# design.net
KiCad netlist of a schematic drawn in EasyEDA Pro
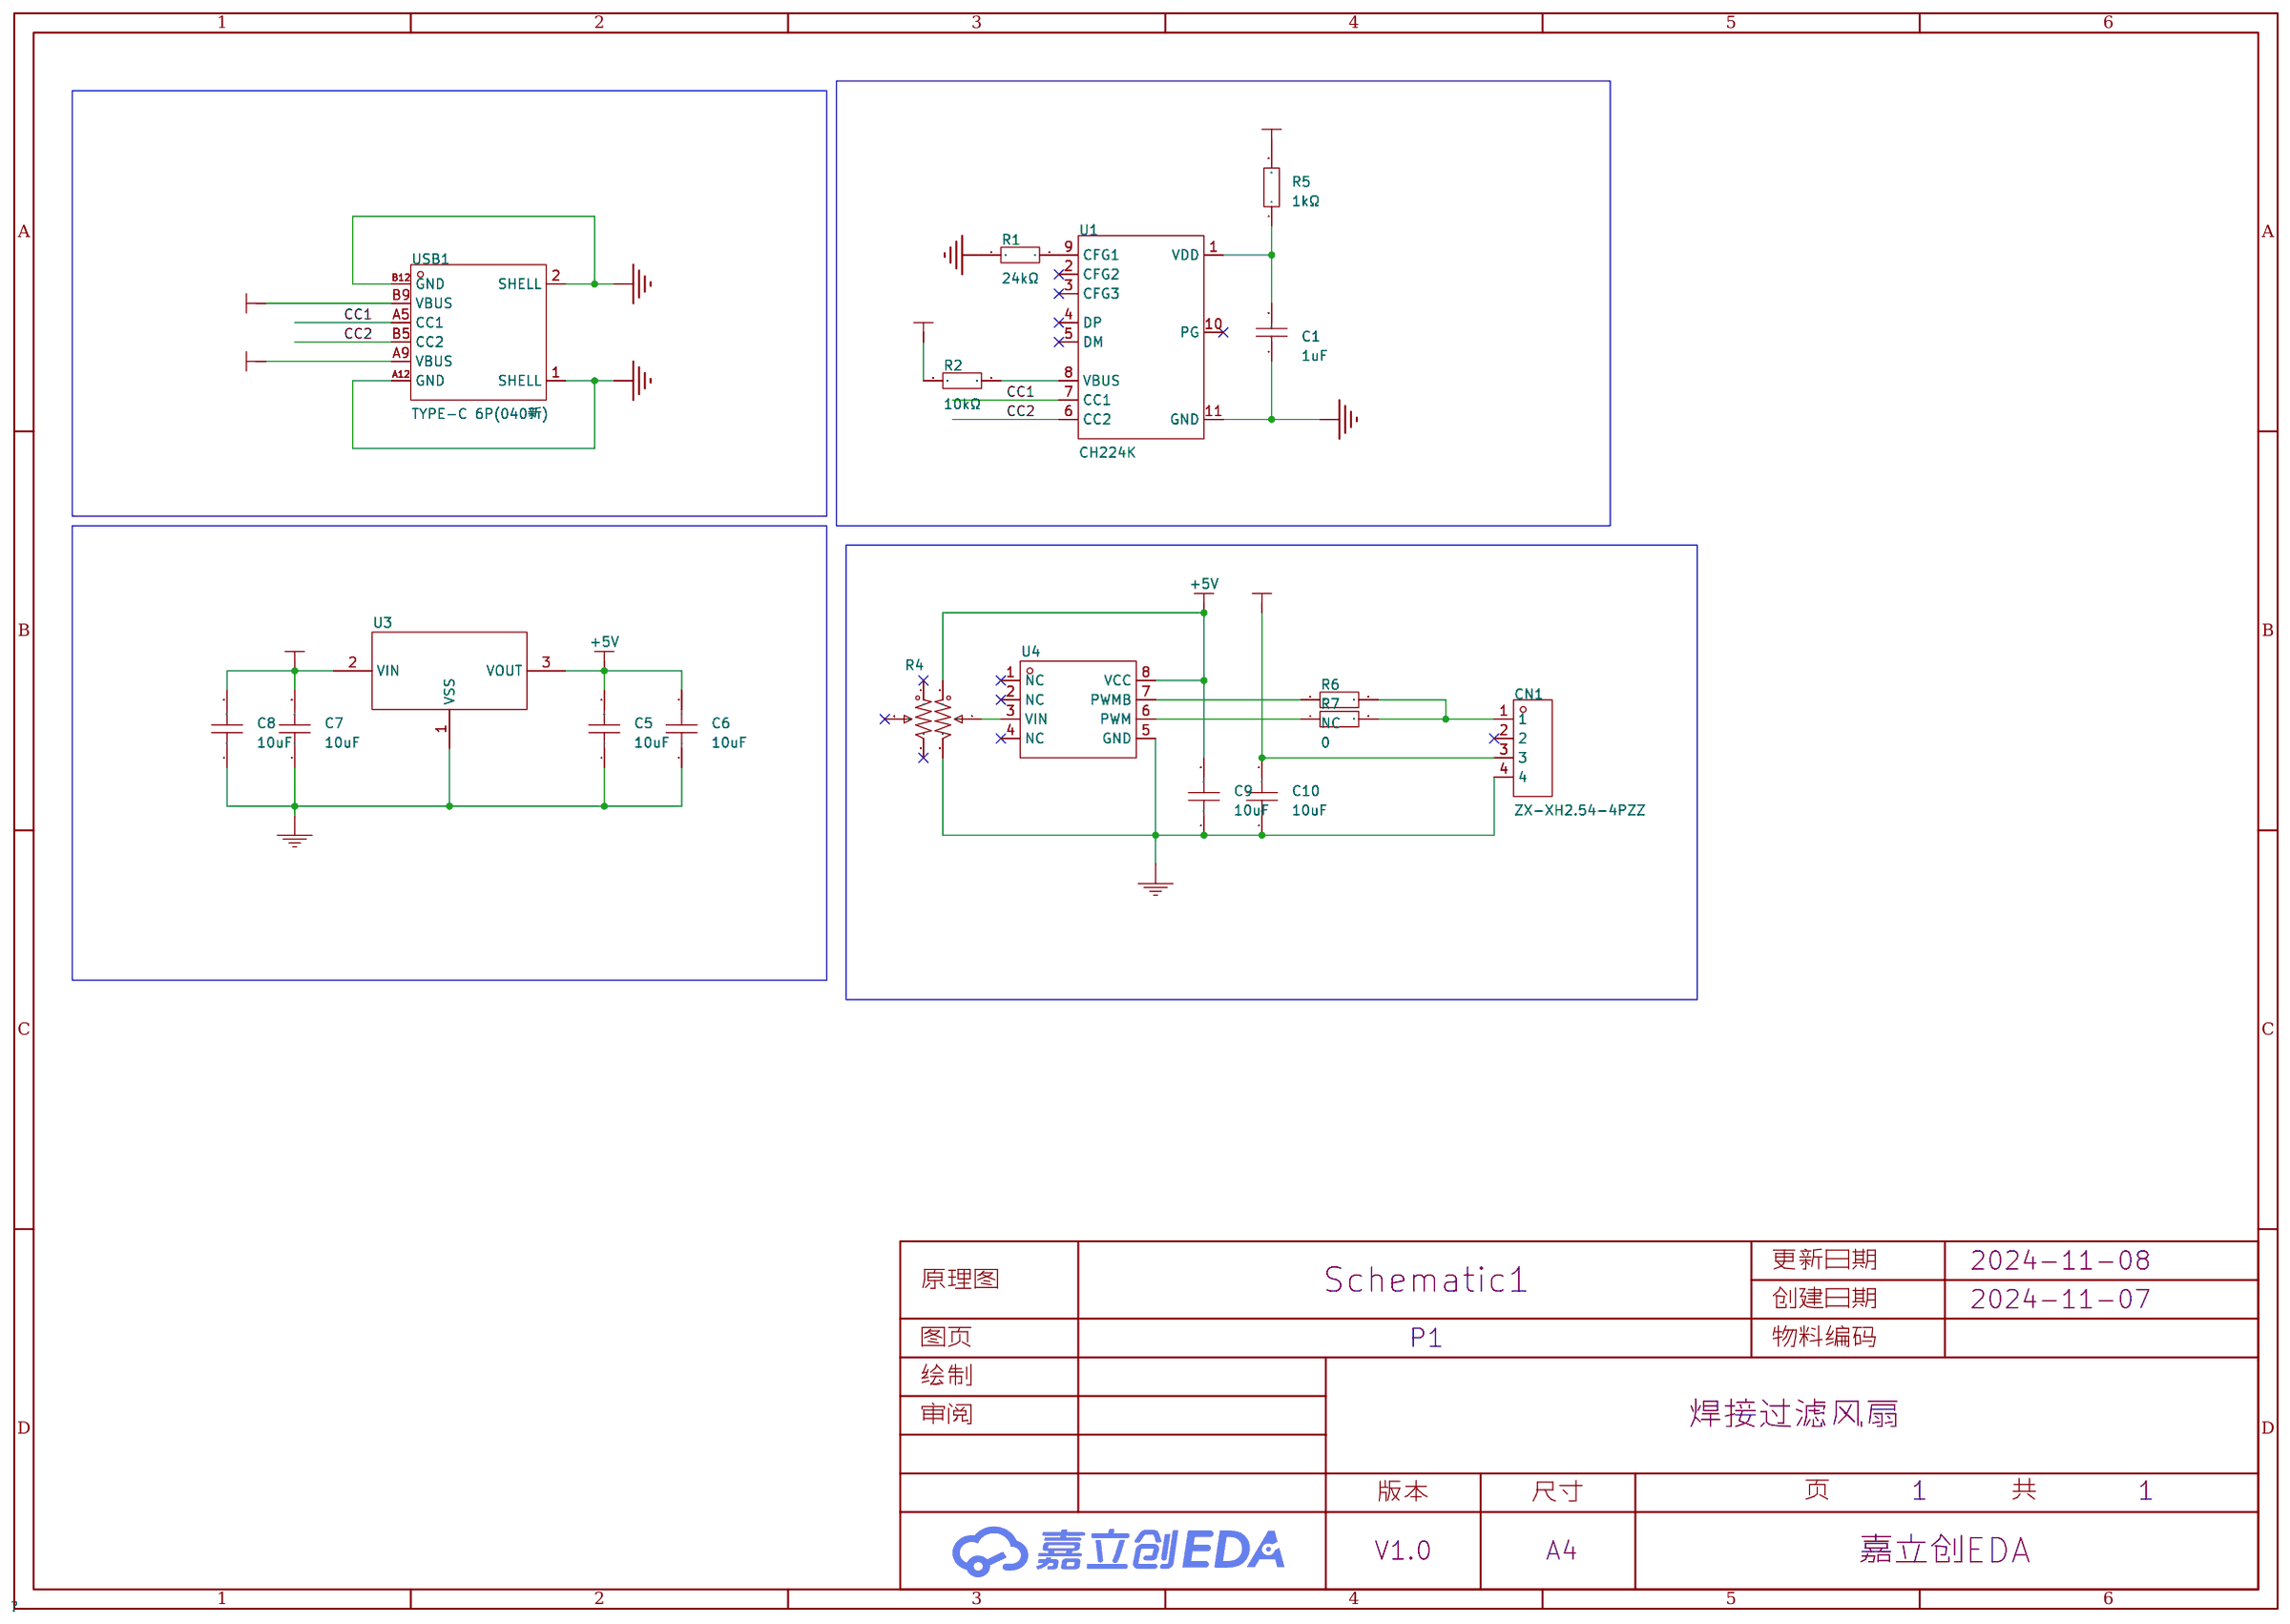
[diagram p0: schematic sheet]

(export (version "E")
  (design (tool "Eeschema 10.0.6"))
  (components
    (comp (ref "C1")
      (value "1uF")
      (footprint "easyedapro:C0805")
      (description "容值:1uF;精度:±10%;额定电压:50V;材质(温度系数):X7R;")
      (fields
        (field (name "Manufacturer Part") "CL21B105KBFNNNE")
        (field (name "Manufacturer") "SAMSUNG(三星)")
      )
      (libsource (lib "easyedapro") (part "CL21B105KBFNNNE"))
    )
    (comp (ref "C5")
      (value "10uF")
      (footprint "easyedapro:C0805")
      (description "容值:10uF;精度:±10%;额定电压:35V;材质(温度系数):X5R;")
      (fields
        (field (name "Manufacturer Part") "CGA0805X5R106K350MT")
        (field (name "Manufacturer") "HRE(芯声)")
      )
      (libsource (lib "easyedapro") (part "CGA0805X5R106K350MT"))
    )
    (comp (ref "C6")
      (value "10uF")
      (footprint "easyedapro:C0805")
      (description "容值:10uF;精度:±10%;额定电压:35V;材质(温度系数):X5R;")
      (fields
        (field (name "Manufacturer Part") "CGA0805X5R106K350MT")
        (field (name "Manufacturer") "HRE(芯声)")
      )
      (libsource (lib "easyedapro") (part "CGA0805X5R106K350MT"))
    )
    (comp (ref "C7")
      (value "10uF")
      (footprint "easyedapro:C0805")
      (description "容值:10uF;精度:±10%;额定电压:35V;材质(温度系数):X5R;")
      (fields
        (field (name "Manufacturer Part") "CGA0805X5R106K350MT")
        (field (name "Manufacturer") "HRE(芯声)")
      )
      (libsource (lib "easyedapro") (part "CGA0805X5R106K350MT"))
    )
    (comp (ref "C8")
      (value "10uF")
      (footprint "easyedapro:C0805")
      (description "容值:10uF;精度:±10%;额定电压:35V;材质(温度系数):X5R;")
      (fields
        (field (name "Manufacturer Part") "CGA0805X5R106K350MT")
        (field (name "Manufacturer") "HRE(芯声)")
      )
      (libsource (lib "easyedapro") (part "CGA0805X5R106K350MT"))
    )
    (comp (ref "C9")
      (value "10uF")
      (footprint "easyedapro:C0805")
      (description "容值:10uF;精度:±10%;额定电压:35V;材质(温度系数):X5R;")
      (fields
        (field (name "Manufacturer Part") "CGA0805X5R106K350MT")
        (field (name "Manufacturer") "HRE(芯声)")
      )
      (libsource (lib "easyedapro") (part "CGA0805X5R106K350MT"))
    )
    (comp (ref "C10")
      (value "10uF")
      (footprint "easyedapro:C0805")
      (description "容值:10uF;精度:±10%;额定电压:35V;材质(温度系数):X5R;")
      (fields
        (field (name "Manufacturer Part") "CGA0805X5R106K350MT")
        (field (name "Manufacturer") "HRE(芯声)")
      )
      (libsource (lib "easyedapro") (part "CGA0805X5R106K350MT"))
    )
    (comp (ref "CN1")
      (value "ZX-XH2.54-4PZZ")
      (footprint "easyedapro:CONN-TH_4P-P2.50_4PIN")
      (fields (field (name "Manufacturer") "Megastar(兆星)"))
      (libsource (lib "easyedapro") (part "ZX-XH2.54-4PZZ"))
    )
    (comp (ref "R1")
      (value "24kΩ")
      (footprint "easyedapro:R0805")
      (description "电阻类型:厚膜电阻;阻值:24kΩ;精度:±1%;功率:125mW;最大工作电压:150V;温度系数:±100ppm/°C;")
      (fields
        (field (name "Manufacturer Part") "0805W8F2402T5E")
        (field (name "Manufacturer") "UNI-ROYAL(厚声)")
      )
      (libsource (lib "easyedapro") (part "0805W8F2402T5E"))
    )
    (comp (ref "R2")
      (value "10kΩ")
      (footprint "easyedapro:R0805")
      (description "电阻类型:厚膜电阻;阻值:10kΩ;精度:±5%;功率:125mW;最大工作电压:150V;温度系数:±100ppm/°C;")
      (fields
        (field (name "Manufacturer Part") "0805W8J0103T5E")
        (field (name "Manufacturer") "UNI-ROYAL(厚声)")
      )
      (libsource (lib "easyedapro") (part "0805W8J0103T5E"))
    )
    (comp (ref "R4")
      (value "100kΩ")
      (fields (field (name "Manufacturer") "ALPSALPINE(阿尔卑斯阿尔派)"))
      (libsource (lib "easyedapro") (part "RK09712200MY"))
    )
    (comp (ref "R5")
      (value "1kΩ")
      (footprint "easyedapro:R0805")
      (description "电阻类型:厚膜电阻;阻值:1kΩ;精度:±1%;功率:125mW;最大工作电压:150V;温度系数:±100ppm/°C;")
      (fields
        (field (name "Manufacturer Part") "0805W8F1001T5E")
        (field (name "Manufacturer") "UNI-ROYAL(厚声)")
      )
      (libsource (lib "easyedapro") (part "0805W8F1001T5E"))
    )
    (comp (ref "R6")
      (value "NC")
      (footprint "easyedapro:R0805")
      (description "电阻类型:厚膜电阻;阻值:10kΩ;精度:±5%;功率:125mW;最大工作电压:150V;温度系数:±100ppm/°C;")
      (fields
        (field (name "Manufacturer Part") "0805W8J0103T5E")
        (field (name "Manufacturer") "UNI-ROYAL(厚声)")
      )
      (libsource (lib "easyedapro") (part "0805W8J0103T5E"))
    )
    (comp (ref "R7")
      (value "0")
      (footprint "easyedapro:R0805")
      (description "电阻类型:厚膜电阻;阻值:10kΩ;精度:±5%;功率:125mW;最大工作电压:150V;温度系数:±100ppm/°C;")
      (fields
        (field (name "Manufacturer Part") "0805W8J0103T5E")
        (field (name "Manufacturer") "UNI-ROYAL(厚声)")
      )
      (libsource (lib "easyedapro") (part "0805W8J0103T5E"))
    )
    (comp (ref "U1")
      (value "CH224K")
      (footprint "easyedapro:ESSOP-10_L4.9-W3.9-P1.0-LS6.0-TL-EP")
      (description "应用功能:USB充电芯片;")
      (fields (field (name "Manufacturer") "WCH(南京沁恒)"))
      (libsource (lib "easyedapro") (part "CH224K"))
    )
    (comp (ref "U3")
      (value "ME6203A50PG")
      (fields (field (name "Manufacturer") "MICRONE(南京微盟)"))
      (libsource (lib "easyedapro") (part "ME6203A50PG"))
    )
    (comp (ref "U4")
      (value "GP9101-F20K-L2H1-SW")
      (footprint "easyedapro:SOP-8_L5.0-W3.9-P1.27-LS6.0-BL")
      (description "GP9101 0-VCC转PWM 20KHz L2H1")
      (fields (field (name "Manufacturer") "Guestgood(客益)"))
      (libsource (lib "easyedapro") (part "GP9101-F20K-L2H1-SW"))
    )
    (comp (ref "USB1")
      (value "TYPE-C 6P(040新)")
      (footprint "easyedapro:USB-C-SMD_TYPE-C-6P")
      (description "连接器类型:Type-C;标准:USB 3.1;公母:母;安装方式:卧贴;触点数量:6P;端口数量:1;额定电流 - 电源:3A;工作温度范围:-40°C~+85°C;")
      (fields (field (name "Manufacturer") "SHOU HAN(首韩)"))
      (libsource (lib "easyedapro") (part "TYPE-C 6P(040新)"))
    )
  )
  (nets
    (net (code "1") (name "+5V") (class "Default")
      (node (ref "C5") (pin "2") (pinfunction "2_2") (pintype "unspecified"))
      (node (ref "C6") (pin "2") (pinfunction "2_2") (pintype "unspecified"))
      (node (ref "C9") (pin "2") (pinfunction "2_2") (pintype "unspecified"))
      (node (ref "R4") (pin "1") (pinfunction "1_1") (pintype "input"))
      (node (ref "U3") (pin "3") (pinfunction "VOUT_3") (pintype "input"))
      (node (ref "U4") (pin "8") (pinfunction "VCC_8") (pintype "input"))
    )
    (net (code "2") (name "+12V") (class "Default")
      (node (ref "C10") (pin "2") (pinfunction "2_2") (pintype "unspecified"))
      (node (ref "C7") (pin "2") (pinfunction "2_2") (pintype "unspecified"))
      (node (ref "C8") (pin "2") (pinfunction "2_2") (pintype "unspecified"))
      (node (ref "CN1") (pin "3") (pinfunction "3_3") (pintype "unspecified"))
      (node (ref "U3") (pin "2") (pinfunction "VIN_2") (pintype "input"))
    )
    (net (code "3") (name "/CC1") (class "Default")
      (node (ref "U1") (pin "7") (pinfunction "CC1_7") (pintype "unspecified"))
      (node (ref "USB1") (pin "A5") (pinfunction "CC1_A5") (pintype "unspecified"))
    )
    (net (code "4") (name "/CC2") (class "Default")
      (node (ref "U1") (pin "6") (pinfunction "CC2_6") (pintype "unspecified"))
      (node (ref "USB1") (pin "B5") (pinfunction "CC2_B5") (pintype "unspecified"))
    )
    (net (code "5") (name "GND") (class "Default")
      (node (ref "C1") (pin "1") (pinfunction "1_1") (pintype "input"))
      (node (ref "C10") (pin "1") (pinfunction "1_1") (pintype "unspecified"))
      (node (ref "C5") (pin "1") (pinfunction "1_1") (pintype "unspecified"))
      (node (ref "C6") (pin "1") (pinfunction "1_1") (pintype "unspecified"))
      (node (ref "C7") (pin "1") (pinfunction "1_1") (pintype "unspecified"))
      (node (ref "C8") (pin "1") (pinfunction "1_1") (pintype "unspecified"))
      (node (ref "C9") (pin "1") (pinfunction "1_1") (pintype "unspecified"))
      (node (ref "CN1") (pin "4") (pinfunction "4_4") (pintype "unspecified"))
      (node (ref "R1") (pin "1") (pinfunction "1_1") (pintype "input"))
      (node (ref "R4") (pin "3") (pinfunction "3_3") (pintype "input"))
      (node (ref "U1") (pin "11") (pinfunction "GND_11") (pintype "unspecified"))
      (node (ref "U3") (pin "1") (pinfunction "VSS_1") (pintype "input"))
      (node (ref "U4") (pin "5") (pinfunction "GND_5") (pintype "input"))
      (node (ref "USB1") (pin "1") (pinfunction "SHELL_1") (pintype "unspecified"))
      (node (ref "USB1") (pin "2") (pinfunction "SHELL_2") (pintype "unspecified"))
      (node (ref "USB1") (pin "A12") (pinfunction "GND_A12") (pintype "unspecified"))
      (node (ref "USB1") (pin "B12") (pinfunction "GND_B12") (pintype "unspecified"))
    )
    (net (code "6") (name "Net-(CN1-Pad1)") (class "Default")
      (node (ref "CN1") (pin "1") (pinfunction "1_1") (pintype "unspecified"))
      (node (ref "R6") (pin "2") (pinfunction "2_2") (pintype "input"))
      (node (ref "R7") (pin "2") (pinfunction "2_2") (pintype "input"))
    )
    (net (code "7") (name "Net-(U1-CFG1)") (class "Default")
      (node (ref "R1") (pin "2") (pinfunction "2_2") (pintype "input"))
      (node (ref "U1") (pin "9") (pinfunction "CFG1_9") (pintype "unspecified"))
    )
    (net (code "8") (name "Net-(U1-VBUS)") (class "Default")
      (node (ref "R2") (pin "2") (pinfunction "2_2") (pintype "input"))
      (node (ref "U1") (pin "8") (pinfunction "VBUS_8") (pintype "unspecified"))
    )
    (net (code "9") (name "Net-(U1-VDD)") (class "Default")
      (node (ref "C1") (pin "2") (pinfunction "2_2") (pintype "input"))
      (node (ref "R5") (pin "1") (pinfunction "1_1") (pintype "input"))
      (node (ref "U1") (pin "1") (pinfunction "VDD_1") (pintype "unspecified"))
    )
    (net (code "10") (name "Net-(U4-PWM)") (class "Default")
      (node (ref "R7") (pin "1") (pinfunction "1_1") (pintype "input"))
      (node (ref "U4") (pin "6") (pinfunction "PWM_6") (pintype "input"))
    )
    (net (code "11") (name "Net-(U4-PWMB)") (class "Default")
      (node (ref "R6") (pin "1") (pinfunction "1_1") (pintype "input"))
      (node (ref "U4") (pin "7") (pinfunction "PWMB_7") (pintype "input"))
    )
    (net (code "12") (name "Net-(U4-VIN)") (class "Default")
      (node (ref "R4") (pin "2") (pinfunction "2_2") (pintype "input"))
      (node (ref "U4") (pin "3") (pinfunction "VIN_3") (pintype "input"))
    )
    (net (code "13") (name "VBUS") (class "Default")
      (node (ref "R2") (pin "1") (pinfunction "1_1") (pintype "input"))
      (node (ref "R5") (pin "2") (pinfunction "2_2") (pintype "input"))
      (node (ref "USB1") (pin "A9") (pinfunction "VBUS_A9") (pintype "unspecified"))
      (node (ref "USB1") (pin "B9") (pinfunction "VBUS_B9") (pintype "unspecified"))
    )
    (net (code "14") (name "unconnected-(CN1-Pad2)") (class "Default")
      (node (ref "CN1") (pin "2") (pinfunction "2_2") (pintype "unspecified+no_connect"))
    )
    (net (code "15") (name "unconnected-(R4-Pad4)") (class "Default")
      (node (ref "R4") (pin "4") (pinfunction "4_4") (pintype "input+no_connect"))
    )
    (net (code "16") (name "unconnected-(R4-Pad5)") (class "Default")
      (node (ref "R4") (pin "5") (pinfunction "5_5") (pintype "input+no_connect"))
    )
    (net (code "17") (name "unconnected-(R4-Pad6)") (class "Default")
      (node (ref "R4") (pin "6") (pinfunction "6_6") (pintype "input+no_connect"))
    )
    (net (code "18") (name "unconnected-(U1-CFG2-Pad2)") (class "Default")
      (node (ref "U1") (pin "2") (pinfunction "CFG2_2") (pintype "unspecified+no_connect"))
    )
    (net (code "19") (name "unconnected-(U1-CFG3-Pad3)") (class "Default")
      (node (ref "U1") (pin "3") (pinfunction "CFG3_3") (pintype "unspecified+no_connect"))
    )
    (net (code "20") (name "unconnected-(U1-DM-Pad5)") (class "Default")
      (node (ref "U1") (pin "5") (pinfunction "DM_5") (pintype "unspecified+no_connect"))
    )
    (net (code "21") (name "unconnected-(U1-DP-Pad4)") (class "Default")
      (node (ref "U1") (pin "4") (pinfunction "DP_4") (pintype "unspecified+no_connect"))
    )
    (net (code "22") (name "unconnected-(U1-PG-Pad10)") (class "Default")
      (node (ref "U1") (pin "10") (pinfunction "PG_10") (pintype "unspecified+no_connect"))
    )
    (net (code "23") (name "unconnected-(U4-NC-Pad1)") (class "Default")
      (node (ref "U4") (pin "1") (pinfunction "NC_1") (pintype "input+no_connect"))
    )
    (net (code "24") (name "unconnected-(U4-NC-Pad2)") (class "Default")
      (node (ref "U4") (pin "2") (pinfunction "NC_2") (pintype "input+no_connect"))
    )
    (net (code "25") (name "unconnected-(U4-NC-Pad4)") (class "Default")
      (node (ref "U4") (pin "4") (pinfunction "NC_4") (pintype "input+no_connect"))
    )
  )
)
